# 14pin_2x7_1_27mm_to_2_54mm.net
KiCad netlist of a schematic drawn in Altium Designer
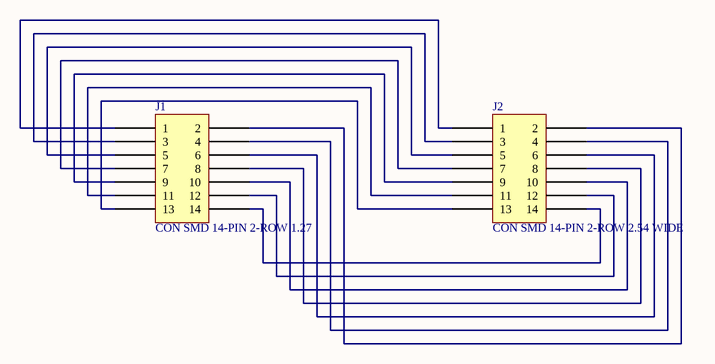
[diagram p0: 14pin_2x7_1.27mm_to_2.54mm.SchDoc]

(export (version "E")
  (design (tool "Eeschema 10.0.6"))
  (components
    (comp (ref "J1")
      (value "CON SMD 14-PIN 2-ROW 1.27")
      (footprint "SMD HEADER 2x7 1.27")
      (description "M50-3600742")
      (libsource (lib "AD_Library") (part "CON SMD 14-PIN 2-ROW 1.27"))
    )
    (comp (ref "J2")
      (value "CON SMD 14-PIN 2-ROW 2.54 WIDE")
      (footprint "SMD HEADER 2x7 2.54 WIDE")
      (description "HTST-107-01-SM-DV-P")
      (libsource (lib "AD_Library") (part "CON SMD 14-PIN 2-ROW 2.54 WIDE"))
    )
  )
  (nets
    (net (code "1") (name "Net-(J1-Pad1)") (class "Default")
      (node (ref "J1") (pin "1") (pinfunction "1_1") (pintype "passive"))
      (node (ref "J2") (pin "1") (pinfunction "1_1") (pintype "passive"))
    )
    (net (code "2") (name "Net-(J1-Pad2)") (class "Default")
      (node (ref "J1") (pin "2") (pinfunction "2_2") (pintype "passive"))
      (node (ref "J2") (pin "2") (pinfunction "2_2") (pintype "passive"))
    )
    (net (code "3") (name "Net-(J1-Pad3)") (class "Default")
      (node (ref "J1") (pin "3") (pinfunction "3_3") (pintype "passive"))
      (node (ref "J2") (pin "3") (pinfunction "3_3") (pintype "passive"))
    )
    (net (code "4") (name "Net-(J1-Pad4)") (class "Default")
      (node (ref "J1") (pin "4") (pinfunction "4_4") (pintype "passive"))
      (node (ref "J2") (pin "4") (pinfunction "4_4") (pintype "passive"))
    )
    (net (code "5") (name "Net-(J1-Pad5)") (class "Default")
      (node (ref "J1") (pin "5") (pinfunction "5_5") (pintype "passive"))
      (node (ref "J2") (pin "5") (pinfunction "5_5") (pintype "passive"))
    )
    (net (code "6") (name "Net-(J1-Pad6)") (class "Default")
      (node (ref "J1") (pin "6") (pinfunction "6_6") (pintype "passive"))
      (node (ref "J2") (pin "6") (pinfunction "6_6") (pintype "passive"))
    )
    (net (code "7") (name "Net-(J1-Pad7)") (class "Default")
      (node (ref "J1") (pin "7") (pinfunction "7_7") (pintype "passive"))
      (node (ref "J2") (pin "7") (pinfunction "7_7") (pintype "passive"))
    )
    (net (code "8") (name "Net-(J1-Pad8)") (class "Default")
      (node (ref "J1") (pin "8") (pinfunction "8_8") (pintype "passive"))
      (node (ref "J2") (pin "8") (pinfunction "8_8") (pintype "passive"))
    )
    (net (code "9") (name "Net-(J1-Pad9)") (class "Default")
      (node (ref "J1") (pin "9") (pinfunction "9_9") (pintype "passive"))
      (node (ref "J2") (pin "9") (pinfunction "9_9") (pintype "passive"))
    )
    (net (code "10") (name "Net-(J1-Pad10)") (class "Default")
      (node (ref "J1") (pin "10") (pinfunction "10_10") (pintype "passive"))
      (node (ref "J2") (pin "10") (pinfunction "10_10") (pintype "passive"))
    )
    (net (code "11") (name "Net-(J1-Pad11)") (class "Default")
      (node (ref "J1") (pin "11") (pinfunction "11_11") (pintype "passive"))
      (node (ref "J2") (pin "11") (pinfunction "11_11") (pintype "passive"))
    )
    (net (code "12") (name "Net-(J1-Pad12)") (class "Default")
      (node (ref "J1") (pin "12") (pinfunction "12_12") (pintype "passive"))
      (node (ref "J2") (pin "12") (pinfunction "12_12") (pintype "passive"))
    )
    (net (code "13") (name "Net-(J1-Pad13)") (class "Default")
      (node (ref "J1") (pin "13") (pinfunction "13_13") (pintype "passive"))
      (node (ref "J2") (pin "13") (pinfunction "13_13") (pintype "passive"))
    )
    (net (code "14") (name "Net-(J1-Pad14)") (class "Default")
      (node (ref "J1") (pin "14") (pinfunction "14_14") (pintype "passive"))
      (node (ref "J2") (pin "14") (pinfunction "14_14") (pintype "passive"))
    )
  )
)
